# LM3404BraceDriver.net
KiCad netlist of a schematic drawn in EAGLE
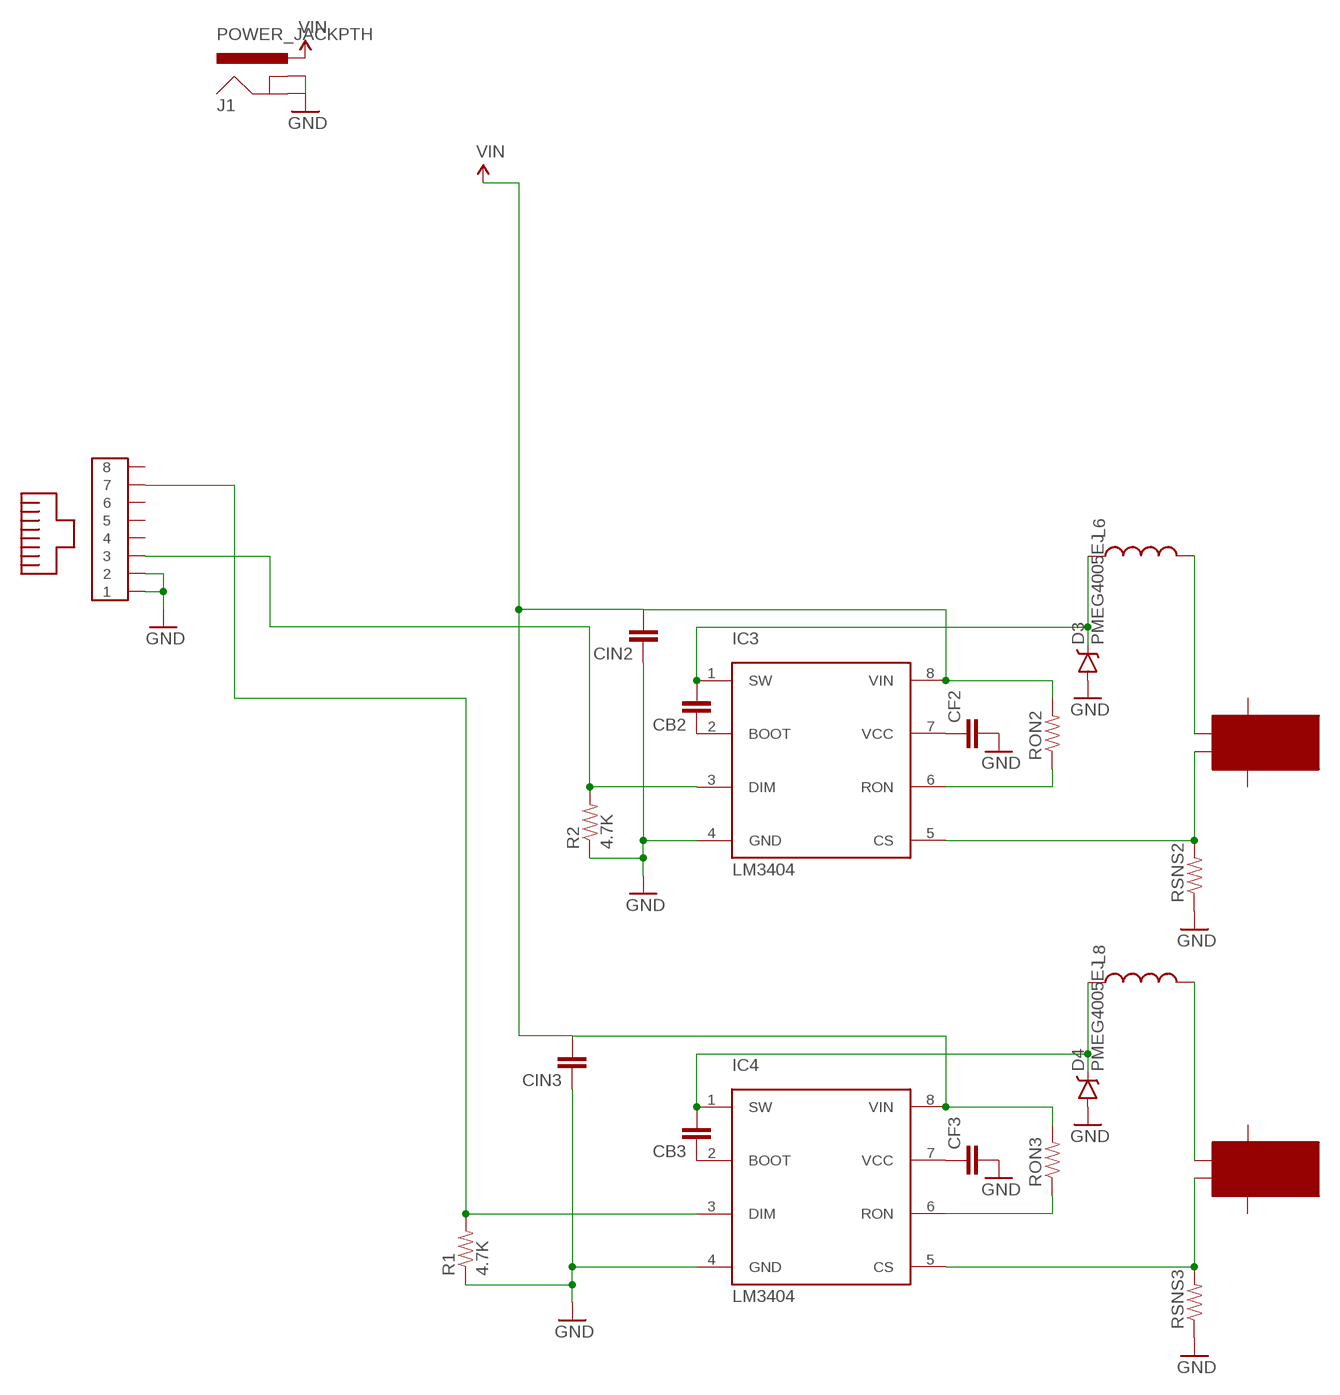
[diagram p0: schematic, sheet 1]

(export (version "E")
  (design (tool "Eeschema 10.0.6"))
  (components
    (comp (ref "CB2")
      (value "CAP0603-CAP")
      (footprint "eagle-import:0603-CAP")
      (libsource (lib "eagle-import") (part "CAP0603-CAP"))
    )
    (comp (ref "CB3")
      (value "CAP0603-CAP")
      (footprint "eagle-import:0603-CAP")
      (libsource (lib "eagle-import") (part "CAP0603-CAP"))
    )
    (comp (ref "CF2")
      (value "CAP1206")
      (footprint "eagle-import:1206")
      (libsource (lib "eagle-import") (part "CAP1206"))
    )
    (comp (ref "CF3")
      (value "CAP1206")
      (footprint "eagle-import:1206")
      (libsource (lib "eagle-import") (part "CAP1206"))
    )
    (comp (ref "CIN2")
      (value "CAP1210")
      (footprint "eagle-import:1210")
      (libsource (lib "eagle-import") (part "CAP1210"))
    )
    (comp (ref "CIN3")
      (value "CAP1210")
      (footprint "eagle-import:1210")
      (libsource (lib "eagle-import") (part "CAP1210"))
    )
    (comp (ref "D3")
      (value "PMEG4005EJ")
      (footprint "eagle-import:SOD-323")
      (libsource (lib "eagle-import") (part "DIODE-SCHOTTKY-PMEG4005EJ"))
    )
    (comp (ref "D4")
      (value "PMEG4005EJ")
      (footprint "eagle-import:SOD-323")
      (libsource (lib "eagle-import") (part "DIODE-SCHOTTKY-PMEG4005EJ"))
    )
    (comp (ref "IC3")
      (value "LM3404")
      (footprint "eagle-import:SO8")
      (libsource (lib "eagle-import") (part "LM3404"))
    )
    (comp (ref "IC4")
      (value "LM3404")
      (footprint "eagle-import:SO8")
      (libsource (lib "eagle-import") (part "LM3404"))
    )
    (comp (ref "J1")
      (value "POWER_JACKPTH")
      (footprint "eagle-import:POWER_JACK_PTH")
      (libsource (lib "eagle-import") (part "POWER_JACKPTH"))
    )
    (comp (ref "L6")
      (value "INDUCTORSDR1105")
      (footprint "eagle-import:B82462G")
      (libsource (lib "eagle-import") (part "INDUCTORSDR1105"))
    )
    (comp (ref "L8")
      (value "INDUCTORSDR1105")
      (footprint "eagle-import:B82462G")
      (libsource (lib "eagle-import") (part "INDUCTORSDR1105"))
    )
    (comp (ref "R1")
      (value "4.7K")
      (footprint "eagle-import:1206")
      (libsource (lib "eagle-import") (part "RESISTOR1206"))
    )
    (comp (ref "R2")
      (value "4.7K")
      (footprint "eagle-import:1206")
      (libsource (lib "eagle-import") (part "RESISTOR1206"))
    )
    (comp (ref "RON2")
      (value "RESISTOR1206")
      (footprint "eagle-import:1206")
      (libsource (lib "eagle-import") (part "RESISTOR1206"))
    )
    (comp (ref "RON3")
      (value "RESISTOR1206")
      (footprint "eagle-import:1206")
      (libsource (lib "eagle-import") (part "RESISTOR1206"))
    )
    (comp (ref "RSNS2")
      (value "RESISTOR1206")
      (footprint "eagle-import:1206")
      (libsource (lib "eagle-import") (part "RESISTOR1206"))
    )
    (comp (ref "RSNS3")
      (value "RESISTOR1206")
      (footprint "eagle-import:1206")
      (libsource (lib "eagle-import") (part "RESISTOR1206"))
    )
    (comp (ref "U$1")
      (value "MOLEX-RJ45-SMT")
      (footprint "eagle-import:MOLEX-RJ45-SMT")
      (libsource (lib "eagle-import") (part "MOLEX-RJ45-SMT"))
    )
    (comp (ref "U$5")
      (value "RCA_JACK")
      (footprint "eagle-import:RCA_JACK")
      (libsource (lib "eagle-import") (part "RCA_JACK"))
    )
    (comp (ref "U$6")
      (value "RCA_JACK")
      (footprint "eagle-import:RCA_JACK")
      (libsource (lib "eagle-import") (part "RCA_JACK"))
    )
  )
  (nets
    (net (code "1") (name "GND") (class "Default")
      (node (ref "CF2") (pin "2") (pinfunction "2_2") (pintype "passive"))
      (node (ref "CF3") (pin "2") (pinfunction "2_2") (pintype "passive"))
      (node (ref "CIN2") (pin "1") (pinfunction "1_1") (pintype "passive"))
      (node (ref "CIN3") (pin "1") (pinfunction "1_1") (pintype "passive"))
      (node (ref "D3") (pin "A") (pinfunction "A_A") (pintype "passive"))
      (node (ref "D4") (pin "A") (pinfunction "A_A") (pintype "passive"))
      (node (ref "IC3") (pin "4") (pinfunction "GND_4") (pintype "bidirectional"))
      (node (ref "IC4") (pin "4") (pinfunction "GND_4") (pintype "bidirectional"))
      (node (ref "J1") (pin "GND") (pinfunction "GND_GND") (pintype "bidirectional"))
      (node (ref "J1") (pin "GNDBREAK") (pinfunction "GNDBREAK_GNDBREAK") (pintype "bidirectional"))
      (node (ref "R1") (pin "1") (pinfunction "1_1") (pintype "passive"))
      (node (ref "R2") (pin "1") (pinfunction "1_1") (pintype "passive"))
      (node (ref "RSNS2") (pin "1") (pinfunction "1_1") (pintype "passive"))
      (node (ref "RSNS3") (pin "1") (pinfunction "1_1") (pintype "passive"))
      (node (ref "U$1") (pin "1") (pinfunction "1_1") (pintype "bidirectional"))
      (node (ref "U$1") (pin "2") (pinfunction "2_2") (pintype "bidirectional"))
    )
    (net (code "2") (name "Net-(IC3-BOOT)") (class "Default")
      (node (ref "CB2") (pin "1") (pinfunction "1_1") (pintype "passive"))
      (node (ref "IC3") (pin "2") (pinfunction "BOOT_2") (pintype "bidirectional"))
    )
    (net (code "3") (name "Net-(IC3-CS)") (class "Default")
      (node (ref "IC3") (pin "5") (pinfunction "CS_5") (pintype "bidirectional"))
      (node (ref "RSNS2") (pin "2") (pinfunction "2_2") (pintype "passive"))
      (node (ref "U$6") (pin "INNER") (pinfunction "INNER_INNER") (pintype "bidirectional"))
    )
    (net (code "4") (name "Net-(IC3-DIM)") (class "Default")
      (node (ref "IC3") (pin "3") (pinfunction "DIM_3") (pintype "bidirectional"))
      (node (ref "R2") (pin "2") (pinfunction "2_2") (pintype "passive"))
      (node (ref "U$1") (pin "3") (pinfunction "3_3") (pintype "bidirectional"))
    )
    (net (code "5") (name "Net-(IC3-RON)") (class "Default")
      (node (ref "IC3") (pin "6") (pinfunction "RON_6") (pintype "bidirectional"))
      (node (ref "RON2") (pin "1") (pinfunction "1_1") (pintype "passive"))
    )
    (net (code "6") (name "Net-(IC3-SW)") (class "Default")
      (node (ref "CB2") (pin "2") (pinfunction "2_2") (pintype "passive"))
      (node (ref "D3") (pin "C") (pinfunction "C_C") (pintype "passive"))
      (node (ref "IC3") (pin "1") (pinfunction "SW_1") (pintype "bidirectional"))
      (node (ref "L6") (pin "P$1") (pinfunction "1_P$1") (pintype "passive"))
    )
    (net (code "7") (name "Net-(IC3-VCC)") (class "Default")
      (node (ref "CF2") (pin "1") (pinfunction "1_1") (pintype "passive"))
      (node (ref "IC3") (pin "7") (pinfunction "VCC_7") (pintype "bidirectional"))
    )
    (net (code "8") (name "Net-(IC4-BOOT)") (class "Default")
      (node (ref "CB3") (pin "1") (pinfunction "1_1") (pintype "passive"))
      (node (ref "IC4") (pin "2") (pinfunction "BOOT_2") (pintype "bidirectional"))
    )
    (net (code "9") (name "Net-(IC4-CS)") (class "Default")
      (node (ref "IC4") (pin "5") (pinfunction "CS_5") (pintype "bidirectional"))
      (node (ref "RSNS3") (pin "2") (pinfunction "2_2") (pintype "passive"))
      (node (ref "U$5") (pin "INNER") (pinfunction "INNER_INNER") (pintype "bidirectional"))
    )
    (net (code "10") (name "Net-(IC4-DIM)") (class "Default")
      (node (ref "IC4") (pin "3") (pinfunction "DIM_3") (pintype "bidirectional"))
      (node (ref "R1") (pin "2") (pinfunction "2_2") (pintype "passive"))
      (node (ref "U$1") (pin "7") (pinfunction "7_7") (pintype "bidirectional"))
    )
    (net (code "11") (name "Net-(IC4-RON)") (class "Default")
      (node (ref "IC4") (pin "6") (pinfunction "RON_6") (pintype "bidirectional"))
      (node (ref "RON3") (pin "1") (pinfunction "1_1") (pintype "passive"))
    )
    (net (code "12") (name "Net-(IC4-SW)") (class "Default")
      (node (ref "CB3") (pin "2") (pinfunction "2_2") (pintype "passive"))
      (node (ref "D4") (pin "C") (pinfunction "C_C") (pintype "passive"))
      (node (ref "IC4") (pin "1") (pinfunction "SW_1") (pintype "bidirectional"))
      (node (ref "L8") (pin "P$1") (pinfunction "1_P$1") (pintype "passive"))
    )
    (net (code "13") (name "Net-(IC4-VCC)") (class "Default")
      (node (ref "CF3") (pin "1") (pinfunction "1_1") (pintype "passive"))
      (node (ref "IC4") (pin "7") (pinfunction "VCC_7") (pintype "bidirectional"))
    )
    (net (code "14") (name "Net-(L6-2)") (class "Default")
      (node (ref "L6") (pin "P$2") (pinfunction "2_P$2") (pintype "passive"))
      (node (ref "U$6") (pin "SIG") (pinfunction "SIG_SIG") (pintype "bidirectional"))
    )
    (net (code "15") (name "Net-(L8-2)") (class "Default")
      (node (ref "L8") (pin "P$2") (pinfunction "2_P$2") (pintype "passive"))
      (node (ref "U$5") (pin "SIG") (pinfunction "SIG_SIG") (pintype "bidirectional"))
    )
    (net (code "16") (name "VIN") (class "Default")
      (node (ref "CIN2") (pin "2") (pinfunction "2_2") (pintype "passive"))
      (node (ref "CIN3") (pin "2") (pinfunction "2_2") (pintype "passive"))
      (node (ref "IC3") (pin "8") (pinfunction "VIN_8") (pintype "bidirectional"))
      (node (ref "IC4") (pin "8") (pinfunction "VIN_8") (pintype "bidirectional"))
      (node (ref "J1") (pin "PWR") (pinfunction "PWR_PWR") (pintype "bidirectional"))
      (node (ref "RON2") (pin "2") (pinfunction "2_2") (pintype "passive"))
      (node (ref "RON3") (pin "2") (pinfunction "2_2") (pintype "passive"))
    )
    (net (code "17") (name "unconnected-(U$1-Pad4)") (class "Default")
      (node (ref "U$1") (pin "4") (pinfunction "4_4") (pintype "bidirectional"))
    )
    (net (code "18") (name "unconnected-(U$1-Pad5)") (class "Default")
      (node (ref "U$1") (pin "5") (pinfunction "5_5") (pintype "bidirectional"))
    )
    (net (code "19") (name "unconnected-(U$1-Pad6)") (class "Default")
      (node (ref "U$1") (pin "6") (pinfunction "6_6") (pintype "bidirectional"))
    )
    (net (code "20") (name "unconnected-(U$1-Pad8)") (class "Default")
      (node (ref "U$1") (pin "8") (pinfunction "8_8") (pintype "bidirectional"))
    )
    (net (code "21") (name "unconnected-(U$5-PadSWA)") (class "Default")
      (node (ref "U$5") (pin "SWA") (pinfunction "SWA_SWA") (pintype "bidirectional"))
    )
    (net (code "22") (name "unconnected-(U$5-PadSWB)") (class "Default")
      (node (ref "U$5") (pin "SWB") (pinfunction "SWB_SWB") (pintype "bidirectional"))
    )
    (net (code "23") (name "unconnected-(U$6-PadSWA)") (class "Default")
      (node (ref "U$6") (pin "SWA") (pinfunction "SWA_SWA") (pintype "bidirectional"))
    )
    (net (code "24") (name "unconnected-(U$6-PadSWB)") (class "Default")
      (node (ref "U$6") (pin "SWB") (pinfunction "SWB_SWB") (pintype "bidirectional"))
    )
  )
)
